# snap_v1.net
KiCad netlist of a schematic drawn in EAGLE
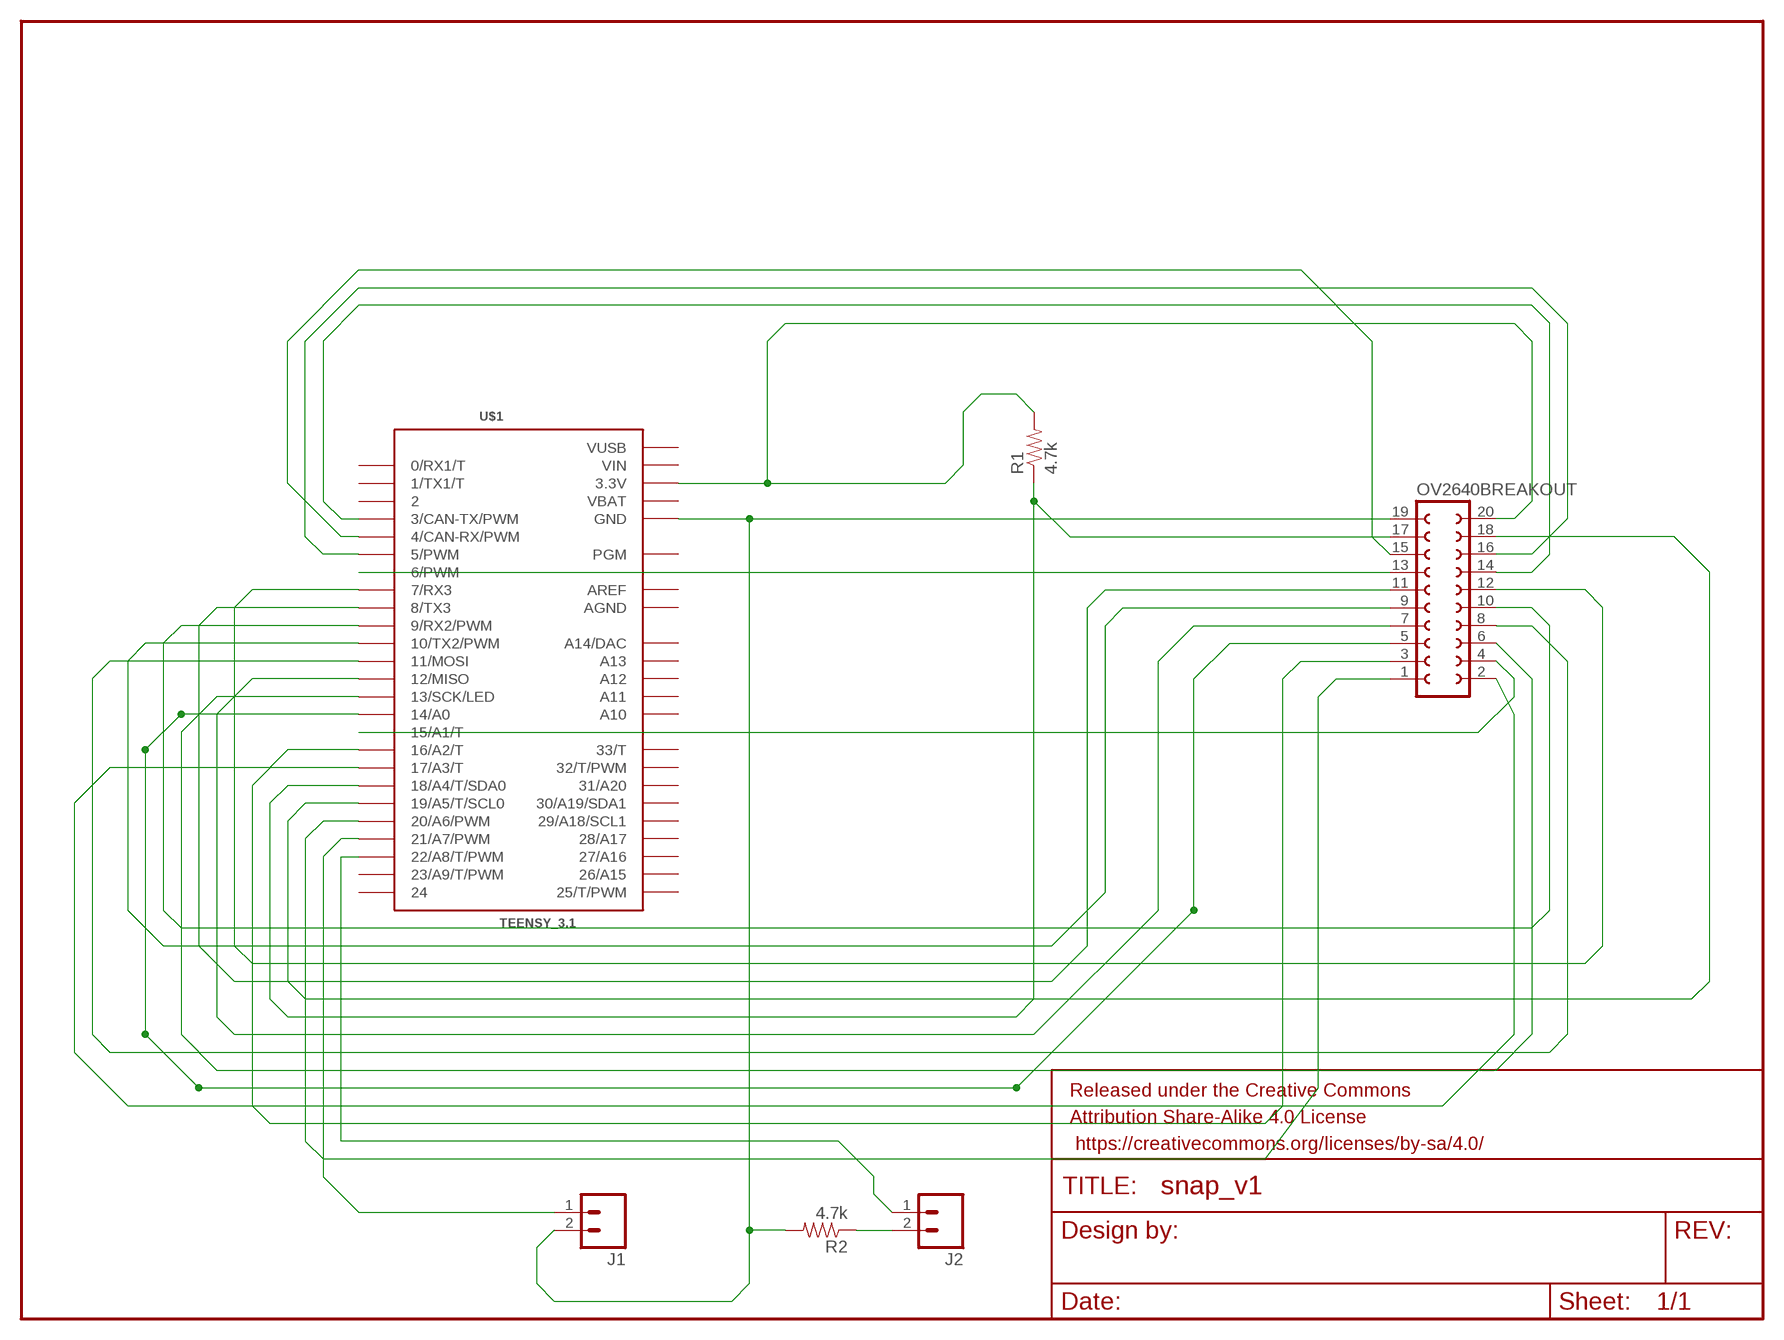
[diagram p0: schematic, sheet 1]

(export (version "E")
  (design (tool "Eeschema 10.0.6"))
  (components
    (comp (ref "FRAME1")
      (value "FRAME-LETTER")
      (footprint "eagle-import:CREATIVE_COMMONS")
      (libsource (lib "eagle-import") (part "FRAME-LETTER"))
    )
    (comp (ref "J1")
      (value "M02PTH")
      (footprint "eagle-import:1X02")
      (libsource (lib "eagle-import") (part "M02PTH"))
    )
    (comp (ref "J2")
      (value "M02PTH")
      (footprint "eagle-import:1X02")
      (libsource (lib "eagle-import") (part "M02PTH"))
    )
    (comp (ref "OV2640BREAKOUT")
      (value "FE10-2")
      (footprint "eagle-import:FE10-2")
      (libsource (lib "eagle-import") (part "FE10-2"))
    )
    (comp (ref "R1")
      (value "4.7k")
      (footprint "eagle-import:AXIAL-0.3EZ")
      (libsource (lib "eagle-import") (part "RESISTOREZ"))
    )
    (comp (ref "R2")
      (value "4.7k")
      (footprint "eagle-import:AXIAL-0.3EZ")
      (libsource (lib "eagle-import") (part "RESISTOREZ"))
    )
    (comp (ref "U$1")
      (value "TEENSY_3.1")
      (footprint "eagle-import:TEENSY_3.0-3.2_ALL_PINS_&_PADS")
      (libsource (lib "eagle-import") (part "TEENSY_3.1-3.2_ALL_PINS&PADS"))
    )
  )
  (nets
    (net (code "1") (name "/AGND") (class "Default")
      (node (ref "U$1") (pin "AGND") (pinfunction "AGND_AGND") (pintype "power_in"))
    )
    (net (code "2") (name "/AREF") (class "Default")
      (node (ref "U$1") (pin "AREF") (pinfunction "AREF_AREF") (pintype "power_in"))
    )
    (net (code "3") (name "/VBAT") (class "Default")
      (node (ref "U$1") (pin "VBAT") (pinfunction "VBAT_VBAT") (pintype "power_in"))
    )
    (net (code "4") (name "/VIN") (class "Default")
      (node (ref "U$1") (pin "VIN") (pinfunction "VIN_VIN") (pintype "power_in"))
    )
    (net (code "5") (name "/VUSB") (class "Default")
      (node (ref "U$1") (pin "VUSB") (pinfunction "VUSB_VUSB") (pintype "power_in"))
    )
    (net (code "6") (name "Net-(OV2640BREAKOUT-Pad5)") (class "Default")
      (node (ref "OV2640BREAKOUT") (pin "5") (pinfunction "5_5") (pintype "passive"))
      (node (ref "U$1") (pin "14/A0") (pinfunction "14/A0_14/A0") (pintype "bidirectional"))
    )
    (net (code "7") (name "Net-(R1-1)") (class "Default")
      (node (ref "OV2640BREAKOUT") (pin "17") (pinfunction "17_17") (pintype "passive"))
      (node (ref "R1") (pin "P$1") (pinfunction "1_P$1") (pintype "passive"))
      (node (ref "U$1") (pin "18/A4") (pinfunction "18/A4/T/SDA0_18/A4") (pintype "bidirectional"))
    )
    (net (code "8") (name "Net-(R1-2)") (class "Default")
      (node (ref "OV2640BREAKOUT") (pin "20") (pinfunction "20_20") (pintype "passive"))
      (node (ref "R1") (pin "P$2") (pinfunction "2_P$2") (pintype "passive"))
      (node (ref "U$1") (pin "3.3V") (pinfunction "3.3V_3.3V") (pintype "power_in"))
      (node (ref "U$1") (pin "3.3V1") (pinfunction "3.3V_3.3V1") (pintype "power_in"))
      (node (ref "U$1") (pin "3.3V2") (pinfunction "3.3V_3.3V2") (pintype "power_in"))
    )
    (net (code "9") (name "Net-(R2-1)") (class "Default")
      (node (ref "J2") (pin "2") (pinfunction "2_2") (pintype "passive"))
      (node (ref "R2") (pin "P$1") (pinfunction "1_P$1") (pintype "passive"))
    )
    (net (code "10") (name "Net-(R2-2)") (class "Default")
      (node (ref "J1") (pin "2") (pinfunction "2_2") (pintype "passive"))
      (node (ref "OV2640BREAKOUT") (pin "19") (pinfunction "19_19") (pintype "passive"))
      (node (ref "R2") (pin "P$2") (pinfunction "2_P$2") (pintype "passive"))
      (node (ref "U$1") (pin "GND") (pinfunction "GND_GND") (pintype "power_in"))
      (node (ref "U$1") (pin "GND1") (pinfunction "GND_GND1") (pintype "power_in"))
      (node (ref "U$1") (pin "GND2") (pinfunction "GND_GND2") (pintype "power_in"))
    )
    (net (code "11") (name "Net-(U$1-3{slash}CAN-TX{slash}PWM)") (class "Default")
      (node (ref "OV2640BREAKOUT") (pin "14") (pinfunction "14_14") (pintype "passive"))
      (node (ref "U$1") (pin "3") (pinfunction "3/CAN-TX/PWM_3") (pintype "bidirectional"))
    )
    (net (code "12") (name "Net-(U$1-4{slash}CAN-RX{slash}PWM)") (class "Default")
      (node (ref "OV2640BREAKOUT") (pin "15") (pinfunction "15_15") (pintype "passive"))
      (node (ref "U$1") (pin "4") (pinfunction "4/CAN-RX/PWM_4") (pintype "bidirectional"))
    )
    (net (code "13") (name "Net-(U$1-5{slash}PWM)") (class "Default")
      (node (ref "OV2640BREAKOUT") (pin "16") (pinfunction "16_16") (pintype "passive"))
      (node (ref "U$1") (pin "5") (pinfunction "5/PWM_5") (pintype "bidirectional"))
    )
    (net (code "14") (name "Net-(U$1-6{slash}PWM)") (class "Default")
      (node (ref "OV2640BREAKOUT") (pin "13") (pinfunction "13_13") (pintype "passive"))
      (node (ref "U$1") (pin "6") (pinfunction "6/PWM_6") (pintype "bidirectional"))
    )
    (net (code "15") (name "Net-(U$1-7{slash}RX3)") (class "Default")
      (node (ref "OV2640BREAKOUT") (pin "12") (pinfunction "12_12") (pintype "passive"))
      (node (ref "U$1") (pin "7") (pinfunction "7/RX3_7") (pintype "bidirectional"))
    )
    (net (code "16") (name "Net-(U$1-8{slash}TX3)") (class "Default")
      (node (ref "OV2640BREAKOUT") (pin "11") (pinfunction "11_11") (pintype "passive"))
      (node (ref "U$1") (pin "8") (pinfunction "8/TX3_8") (pintype "bidirectional"))
    )
    (net (code "17") (name "Net-(U$1-9{slash}RX2{slash}PWM)") (class "Default")
      (node (ref "OV2640BREAKOUT") (pin "10") (pinfunction "10_10") (pintype "passive"))
      (node (ref "U$1") (pin "9") (pinfunction "9/RX2/PWM_9") (pintype "bidirectional"))
    )
    (net (code "18") (name "Net-(U$1-10{slash}TX2{slash}PWM)") (class "Default")
      (node (ref "OV2640BREAKOUT") (pin "9") (pinfunction "9_9") (pintype "passive"))
      (node (ref "U$1") (pin "10") (pinfunction "10/TX2/PWM_10") (pintype "bidirectional"))
    )
    (net (code "19") (name "Net-(U$1-11{slash}MOSI)") (class "Default")
      (node (ref "OV2640BREAKOUT") (pin "8") (pinfunction "8_8") (pintype "passive"))
      (node (ref "U$1") (pin "11") (pinfunction "11/MOSI_11") (pintype "bidirectional"))
    )
    (net (code "20") (name "Net-(U$1-12{slash}MISO)") (class "Default")
      (node (ref "OV2640BREAKOUT") (pin "7") (pinfunction "7_7") (pintype "passive"))
      (node (ref "U$1") (pin "12") (pinfunction "12/MISO_12") (pintype "bidirectional"))
    )
    (net (code "21") (name "Net-(U$1-13{slash}SCK{slash}LED)") (class "Default")
      (node (ref "OV2640BREAKOUT") (pin "6") (pinfunction "6_6") (pintype "passive"))
      (node (ref "U$1") (pin "13") (pinfunction "13/SCK/LED_13") (pintype "bidirectional"))
    )
    (net (code "22") (name "Net-(U$1-15{slash}A1{slash}T)") (class "Default")
      (node (ref "OV2640BREAKOUT") (pin "4") (pinfunction "4_4") (pintype "passive"))
      (node (ref "U$1") (pin "15/A1") (pinfunction "15/A1/T_15/A1") (pintype "bidirectional"))
    )
    (net (code "23") (name "Net-(U$1-16{slash}A2{slash}T)") (class "Default")
      (node (ref "OV2640BREAKOUT") (pin "3") (pinfunction "3_3") (pintype "passive"))
      (node (ref "U$1") (pin "16/A2") (pinfunction "16/A2/T_16/A2") (pintype "bidirectional"))
    )
    (net (code "24") (name "Net-(U$1-17{slash}A3{slash}T)") (class "Default")
      (node (ref "OV2640BREAKOUT") (pin "2") (pinfunction "2_2") (pintype "passive"))
      (node (ref "U$1") (pin "17/A3") (pinfunction "17/A3/T_17/A3") (pintype "bidirectional"))
    )
    (net (code "25") (name "Net-(U$1-19{slash}A5{slash}T{slash}SCL0)") (class "Default")
      (node (ref "OV2640BREAKOUT") (pin "18") (pinfunction "18_18") (pintype "passive"))
      (node (ref "U$1") (pin "19/A5") (pinfunction "19/A5/T/SCL0_19/A5") (pintype "bidirectional"))
    )
    (net (code "26") (name "Net-(U$1-20{slash}A6{slash}PWM)") (class "Default")
      (node (ref "OV2640BREAKOUT") (pin "1") (pinfunction "1_1") (pintype "passive"))
      (node (ref "U$1") (pin "20/A6") (pinfunction "20/A6/PWM_20/A6") (pintype "bidirectional"))
    )
    (net (code "27") (name "Net-(U$1-21{slash}A7{slash}PWM)") (class "Default")
      (node (ref "J1") (pin "1") (pinfunction "1_1") (pintype "passive"))
      (node (ref "U$1") (pin "21/A7") (pinfunction "21/A7/PWM_21/A7") (pintype "bidirectional"))
    )
    (net (code "28") (name "Net-(U$1-22{slash}A8{slash}T{slash}PWM)") (class "Default")
      (node (ref "J2") (pin "1") (pinfunction "1_1") (pintype "passive"))
      (node (ref "U$1") (pin "22/A8") (pinfunction "22/A8/T/PWM_22/A8") (pintype "bidirectional"))
    )
    (net (code "29") (name "unconnected-(U$1-0{slash}RX1{slash}T-Pad0)") (class "Default")
      (node (ref "U$1") (pin "0") (pinfunction "0/RX1/T_0") (pintype "bidirectional"))
    )
    (net (code "30") (name "unconnected-(U$1-1{slash}TX1{slash}T-Pad1)") (class "Default")
      (node (ref "U$1") (pin "1") (pinfunction "1/TX1/T_1") (pintype "bidirectional"))
    )
    (net (code "31") (name "unconnected-(U$1-23{slash}A9{slash}T{slash}PWM-Pad23{slash}A9)") (class "Default")
      (node (ref "U$1") (pin "23/A9") (pinfunction "23/A9/T/PWM_23/A9") (pintype "bidirectional"))
    )
    (net (code "32") (name "unconnected-(U$1-25{slash}T{slash}PWM-Pad25)") (class "Default")
      (node (ref "U$1") (pin "25") (pinfunction "25/T/PWM_25") (pintype "bidirectional"))
    )
    (net (code "33") (name "unconnected-(U$1-26{slash}A15-Pad26)") (class "Default")
      (node (ref "U$1") (pin "26") (pinfunction "26/A15_26") (pintype "bidirectional"))
    )
    (net (code "34") (name "unconnected-(U$1-27{slash}A16-Pad27)") (class "Default")
      (node (ref "U$1") (pin "27") (pinfunction "27/A16_27") (pintype "bidirectional"))
    )
    (net (code "35") (name "unconnected-(U$1-28{slash}A17-Pad28)") (class "Default")
      (node (ref "U$1") (pin "28") (pinfunction "28/A17_28") (pintype "bidirectional"))
    )
    (net (code "36") (name "unconnected-(U$1-29{slash}A18{slash}SCL1-Pad29)") (class "Default")
      (node (ref "U$1") (pin "29") (pinfunction "29/A18/SCL1_29") (pintype "bidirectional"))
    )
    (net (code "37") (name "unconnected-(U$1-30{slash}A19{slash}SDA1-Pad30)") (class "Default")
      (node (ref "U$1") (pin "30") (pinfunction "30/A19/SDA1_30") (pintype "bidirectional"))
    )
    (net (code "38") (name "unconnected-(U$1-31{slash}A20-Pad31)") (class "Default")
      (node (ref "U$1") (pin "31") (pinfunction "31/A20_31") (pintype "bidirectional"))
    )
    (net (code "39") (name "unconnected-(U$1-32{slash}T{slash}PWM-Pad32)") (class "Default")
      (node (ref "U$1") (pin "32") (pinfunction "32/T/PWM_32") (pintype "bidirectional"))
    )
    (net (code "40") (name "unconnected-(U$1-33{slash}T-Pad33)") (class "Default")
      (node (ref "U$1") (pin "33") (pinfunction "33/T_33") (pintype "bidirectional"))
    )
    (net (code "41") (name "unconnected-(U$1-A14{slash}DAC-PadRESET{slash}DAC)") (class "Default")
      (node (ref "U$1") (pin "RESET/DAC") (pinfunction "A14/DAC_RESET/DAC") (pintype "bidirectional"))
    )
    (net (code "42") (name "unconnected-(U$1-Pad2)") (class "Default")
      (node (ref "U$1") (pin "2") (pinfunction "2_2") (pintype "bidirectional"))
    )
    (net (code "43") (name "unconnected-(U$1-Pad24)") (class "Default")
      (node (ref "U$1") (pin "24") (pinfunction "24_24") (pintype "bidirectional"))
    )
    (net (code "44") (name "unconnected-(U$1-PadA10)") (class "Default")
      (node (ref "U$1") (pin "A10") (pinfunction "A10_A10") (pintype "bidirectional"))
    )
    (net (code "45") (name "unconnected-(U$1-PadA11)") (class "Default")
      (node (ref "U$1") (pin "A11") (pinfunction "A11_A11") (pintype "bidirectional"))
    )
    (net (code "46") (name "unconnected-(U$1-PadA12)") (class "Default")
      (node (ref "U$1") (pin "A12") (pinfunction "A12_A12") (pintype "bidirectional"))
    )
    (net (code "47") (name "unconnected-(U$1-PadA13)") (class "Default")
      (node (ref "U$1") (pin "A13") (pinfunction "A13_A13") (pintype "bidirectional"))
    )
    (net (code "48") (name "unconnected-(U$1-PadPGM)") (class "Default")
      (node (ref "U$1") (pin "PGM") (pinfunction "PGM_PGM") (pintype "bidirectional"))
    )
  )
)
